# MJE13001_SWITCHING_WITH_FEEDBACK.net
KiCad netlist of a schematic drawn in Altium Designer
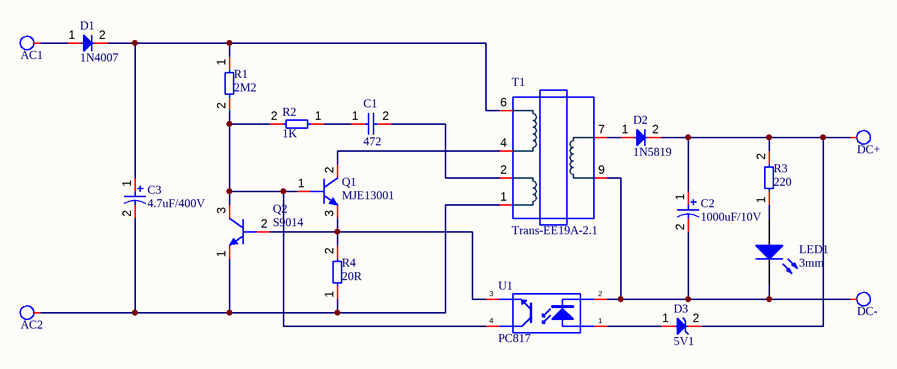
[diagram p0: MJE13001_SWITCHING_WITH_FEEDBACK.SchDoc]

(export (version "E")
  (design (tool "Eeschema 10.0.6"))
  (components
    (comp (ref "AC1")
      (value "SolderPoint")
      (footprint "SolderPoint")
      (libsource (lib "Lib31082020") (part "SolderPoint"))
    )
    (comp (ref "AC2")
      (value "SolderPoint")
      (footprint "SolderPoint")
      (libsource (lib "Lib31082020") (part "SolderPoint"))
    )
    (comp (ref "C1")
      (value "472")
      (footprint "CAP_DISC_PITCH_2.54MM")
      (libsource (lib "Lib31082020") (part "Capacitors(Disc)"))
    )
    (comp (ref "C2")
      (value "1000uF/10V")
      (footprint "CAP_RAD_7mm")
      (libsource (lib "Lib31082020") (part "Capacitor(Radian)"))
    )
    (comp (ref "C3")
      (value "4.7uF/400V")
      (footprint "CAP_RAD_7mm")
      (libsource (lib "Lib31082020") (part "Capacitor(Radian)"))
    )
    (comp (ref "D1") (value "1N4007") (footprint "DO-41") (libsource (lib "Lib31082020") (part "1N4007")))
    (comp (ref "D2") (value "1N5819") (footprint "DO-41") (libsource (lib "Lib31082020") (part "1N4007")))
    (comp (ref "D3")
      (value "5V1")
      (footprint "DO-35 Horizontal")
      (libsource (lib "Lib31082020") (part "Diode Zener"))
    )
    (comp (ref "DC+")
      (value "SolderPoint")
      (footprint "SolderPoint")
      (libsource (lib "Lib31082020") (part "SolderPoint"))
    )
    (comp (ref "DC-")
      (value "SolderPoint")
      (footprint "SolderPoint")
      (libsource (lib "Lib31082020") (part "SolderPoint"))
    )
    (comp (ref "LED1")
      (value "3mm")
      (footprint "LED 3mm Green")
      (libsource (lib "Library 3D") (part "LED 3mm"))
    )
    (comp (ref "Q1")
      (value "MJE13001")
      (footprint "TO-92")
      (libsource (lib "Lib31082020") (part "MJE13001_Type_F"))
    )
    (comp (ref "Q2") (value "S9014") (footprint "TO-92") (libsource (lib "Lib31082020") (part "S9014")))
    (comp (ref "R1")
      (value "2M2")
      (footprint "RES-0.25W-H-MF")
      (libsource (lib "Lib31082020") (part "Resistors THD"))
    )
    (comp (ref "R2") (value "1K") (footprint "RES-0.25W-H-MF") (libsource (lib "") (part "Resistors THD_1")))
    (comp (ref "R3") (value "220") (footprint "R0805") (libsource (lib "Lib31082020") (part "Resistor SMD")))
    (comp (ref "R4") (value "20R") (footprint "RES-0.25W-H-MF") (libsource (lib "") (part "Resistors THD_2")))
    (comp (ref "T1")
      (value "Trans-EE19A-2.1")
      (footprint "TRANS_EE19A-2.1")
      (libsource (lib "Lib31082020") (part "Trans-EE19A-2.1"))
    )
    (comp (ref "U1") (value "PC817") (footprint "DIP4") (libsource (lib "Lib31082020") (part "PC817")))
  )
  (nets
    (net (code "1") (name "Net-(AC1-Pad1)") (class "Default")
      (node (ref "AC1") (pin "1") (pinfunction "1_1") (pintype "passive"))
      (node (ref "D1") (pin "1") (pinfunction "1_1") (pintype "passive"))
    )
    (net (code "2") (name "Net-(C1-Pad1)") (class "Default")
      (node (ref "C1") (pin "1") (pinfunction "1_1") (pintype "passive"))
      (node (ref "R2") (pin "1") (pinfunction "1_1") (pintype "passive"))
    )
    (net (code "3") (name "Net-(C1-Pad2)") (class "Default")
      (node (ref "C1") (pin "2") (pinfunction "2_2") (pintype "passive"))
      (node (ref "T1") (pin "2") (pinfunction "2_2") (pintype "passive"))
    )
    (net (code "4") (name "Net-(C2-Pad1)") (class "Default")
      (node (ref "C2") (pin "1") (pinfunction "1_1") (pintype "passive"))
      (node (ref "D2") (pin "2") (pinfunction "2_2") (pintype "passive"))
      (node (ref "D3") (pin "2") (pinfunction "2_2") (pintype "passive"))
      (node (ref "DC+") (pin "1") (pinfunction "1_1") (pintype "passive"))
      (node (ref "R3") (pin "2") (pinfunction "2_2") (pintype "passive"))
    )
    (net (code "5") (name "Net-(D2-Pad1)") (class "Default")
      (node (ref "D2") (pin "1") (pinfunction "1_1") (pintype "passive"))
      (node (ref "T1") (pin "7") (pinfunction "7_7") (pintype "passive"))
    )
    (net (code "6") (name "Net-(LED1-A)") (class "Default")
      (node (ref "LED1") (pin "1") (pinfunction "A_1") (pintype "passive"))
      (node (ref "R3") (pin "1") (pinfunction "1_1") (pintype "passive"))
    )
    (net (code "7") (name "Net-(LED1-K)") (class "Default")
      (node (ref "C2") (pin "2") (pinfunction "2_2") (pintype "passive"))
      (node (ref "DC-") (pin "1") (pinfunction "1_1") (pintype "passive"))
      (node (ref "LED1") (pin "2") (pinfunction "K_2") (pintype "passive"))
      (node (ref "T1") (pin "9") (pinfunction "9_9") (pintype "passive"))
      (node (ref "U1") (pin "2") (pinfunction "K_2") (pintype "passive"))
    )
    (net (code "8") (name "Net-(Q1-B)") (class "Default")
      (node (ref "Q1") (pin "1") (pinfunction "B_1") (pintype "passive"))
      (node (ref "Q2") (pin "3") (pinfunction "C_3") (pintype "passive"))
      (node (ref "R1") (pin "2") (pinfunction "2_2") (pintype "passive"))
      (node (ref "R2") (pin "2") (pinfunction "2_2") (pintype "passive"))
      (node (ref "U1") (pin "4") (pinfunction "C_4") (pintype "passive"))
    )
    (net (code "9") (name "Net-(Q1-C)") (class "Default")
      (node (ref "Q1") (pin "2") (pinfunction "C_2") (pintype "passive"))
      (node (ref "T1") (pin "4") (pinfunction "4_4") (pintype "passive"))
    )
    (net (code "10") (name "Net-(Q1-E)") (class "Default")
      (node (ref "Q1") (pin "3") (pinfunction "E_3") (pintype "passive"))
      (node (ref "Q2") (pin "2") (pinfunction "B_2") (pintype "passive"))
      (node (ref "R4") (pin "2") (pinfunction "2_2") (pintype "passive"))
      (node (ref "U1") (pin "3") (pinfunction "E_3") (pintype "passive"))
    )
    (net (code "11") (name "Net-(Q2-E)") (class "Default")
      (node (ref "AC2") (pin "1") (pinfunction "1_1") (pintype "passive"))
      (node (ref "C3") (pin "2") (pinfunction "2_2") (pintype "passive"))
      (node (ref "Q2") (pin "1") (pinfunction "E_1") (pintype "passive"))
      (node (ref "R4") (pin "1") (pinfunction "1_1") (pintype "passive"))
      (node (ref "T1") (pin "1") (pinfunction "1_1") (pintype "passive"))
    )
    (net (code "12") (name "Net-(T1-61)") (class "Default")
      (node (ref "C3") (pin "1") (pinfunction "1_1") (pintype "passive"))
      (node (ref "D1") (pin "2") (pinfunction "2_2") (pintype "passive"))
      (node (ref "R1") (pin "1") (pinfunction "1_1") (pintype "passive"))
      (node (ref "T1") (pin "6") (pinfunction "61_6") (pintype "passive"))
    )
    (net (code "13") (name "Net-(U1-A)") (class "Default")
      (node (ref "D3") (pin "1") (pinfunction "1_1") (pintype "passive"))
      (node (ref "U1") (pin "1") (pinfunction "A_1") (pintype "passive"))
    )
  )
)
